# RTC.net
KiCad netlist of a schematic drawn in Altium Designer
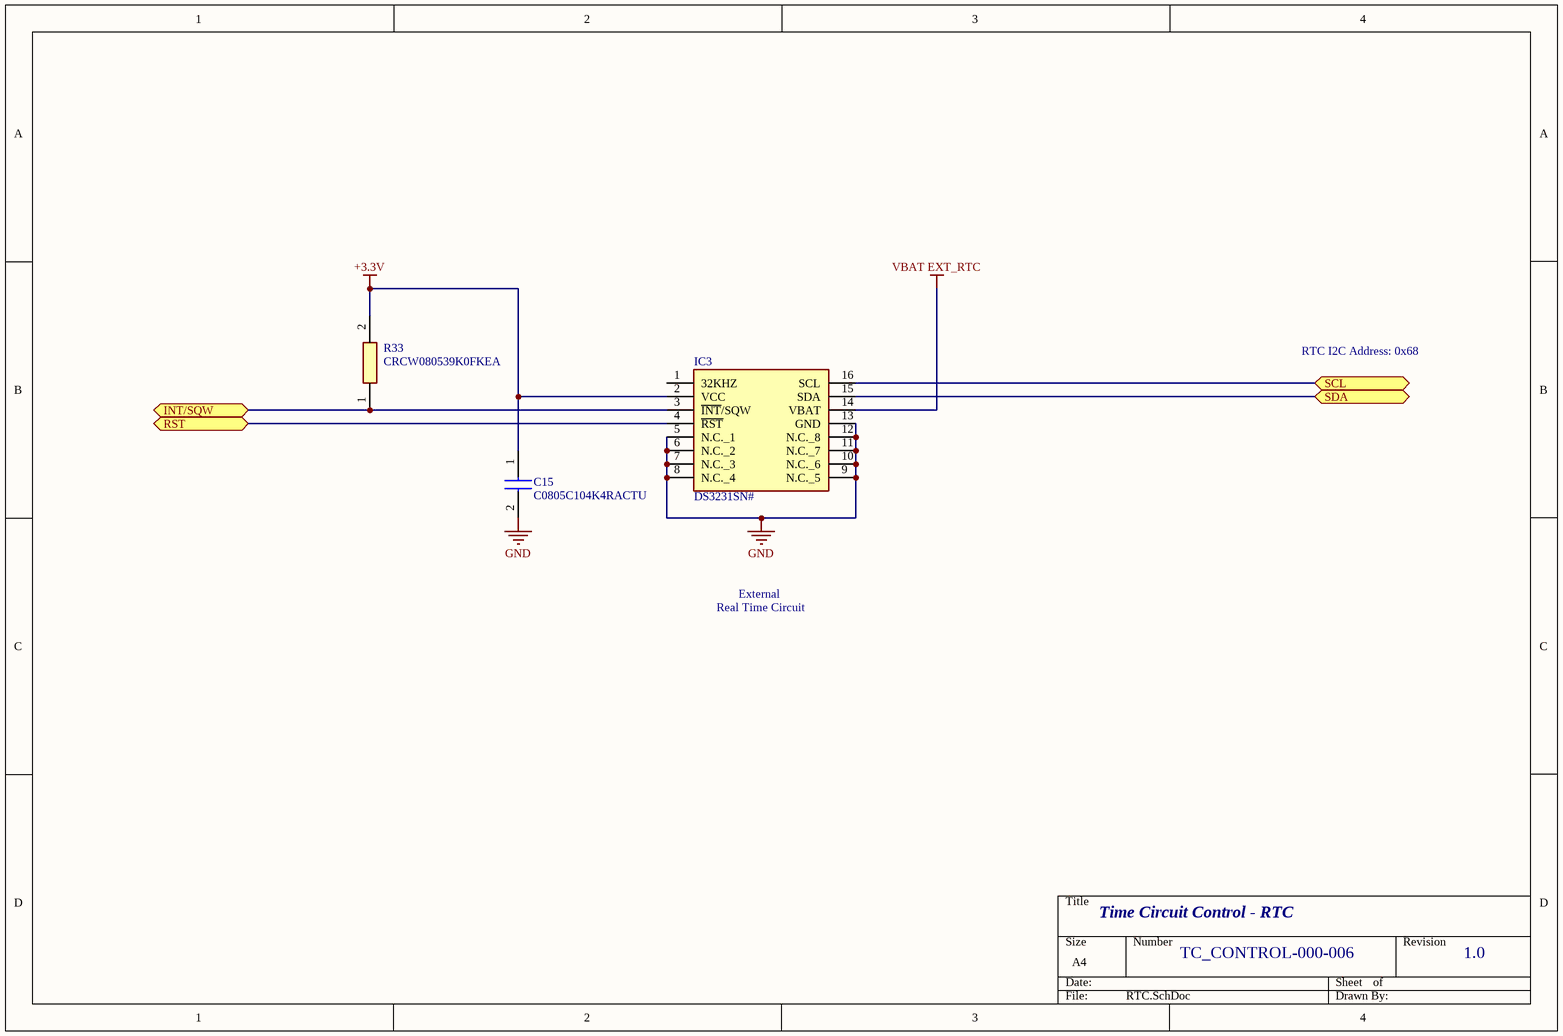
[diagram p0: RTC.SchDoc]

(export (version "E")
  (design (tool "Eeschema 10.0.6"))
  (components
    (comp (ref "C15")
      (value "C0805C104K4RACTU")
      (footprint "SamacSys:CAPC2012X88N")
      (description "Capacitor")
      (fields (field (name "MOUSER PART NUMBER") "80-C0805C104K4R"))
      (libsource (lib "SamacSys") (part "C0805C104K4RACTU"))
    )
    (comp (ref "IC3")
      (value "DS3231SN#")
      (footprint "SamacSys:SOIC127P1032X265-16N")
      (description "Integrated Circuit")
      (fields (field (name "MOUSER PART NUMBER") "700-DS3231SN#"))
      (libsource (lib "SamacSys") (part "DS3231SN#"))
    )
    (comp (ref "R33")
      (value "CRCW080539K0FKEA")
      (footprint "SamacSys:RESC2012X50N")
      (description "Resistor")
      (fields (field (name "MOUSER PART NUMBER") "71-CRCW080539K0FKEA"))
      (libsource (lib "SamacSys") (part "CRCW080539K0FKEA"))
    )
  )
  (nets
    (net (code "1") (name "+3.3V") (class "Default")
      (node (ref "C15") (pin "1") (pinfunction "1_1") (pintype "passive"))
      (node (ref "IC3") (pin "2") (pinfunction "VCC_2") (pintype "passive"))
      (node (ref "R33") (pin "2") (pinfunction "2_2") (pintype "passive"))
    )
    (net (code "2") (name "/INT{slash}SQW") (class "Default")
      (node (ref "IC3") (pin "3") (pinfunction "~{INT}/SQW_3") (pintype "passive"))
      (node (ref "R33") (pin "1") (pinfunction "1_1") (pintype "passive"))
    )
    (net (code "3") (name "/RST") (class "Default")
      (node (ref "IC3") (pin "4") (pinfunction "~{RST}_4") (pintype "passive"))
    )
    (net (code "4") (name "/SCL") (class "Default")
      (node (ref "IC3") (pin "16") (pinfunction "SCL_16") (pintype "passive"))
    )
    (net (code "5") (name "/SDA") (class "Default")
      (node (ref "IC3") (pin "15") (pinfunction "SDA_15") (pintype "passive"))
    )
    (net (code "6") (name "GND") (class "Default")
      (node (ref "C15") (pin "2") (pinfunction "2_2") (pintype "passive"))
      (node (ref "IC3") (pin "10") (pinfunction "N.C._6_10") (pintype "passive"))
      (node (ref "IC3") (pin "11") (pinfunction "N.C._7_11") (pintype "passive"))
      (node (ref "IC3") (pin "12") (pinfunction "N.C._8_12") (pintype "passive"))
      (node (ref "IC3") (pin "13") (pinfunction "GND_13") (pintype "passive"))
      (node (ref "IC3") (pin "5") (pinfunction "N.C._1_5") (pintype "passive"))
      (node (ref "IC3") (pin "6") (pinfunction "N.C._2_6") (pintype "passive"))
      (node (ref "IC3") (pin "7") (pinfunction "N.C._3_7") (pintype "passive"))
      (node (ref "IC3") (pin "8") (pinfunction "N.C._4_8") (pintype "passive"))
      (node (ref "IC3") (pin "9") (pinfunction "N.C._5_9") (pintype "passive"))
    )
    (net (code "7") (name "VBAT EXT_RTC") (class "Default")
      (node (ref "IC3") (pin "14") (pinfunction "VBAT_14") (pintype "passive"))
    )
    (net (code "8") (name "unconnected-(IC3-32KHZ-Pad1)") (class "Default")
      (node (ref "IC3") (pin "1") (pinfunction "32KHZ_1") (pintype "passive"))
    )
  )
)
